# EMAX_12A.net
KiCad netlist of a schematic drawn in Altium Designer
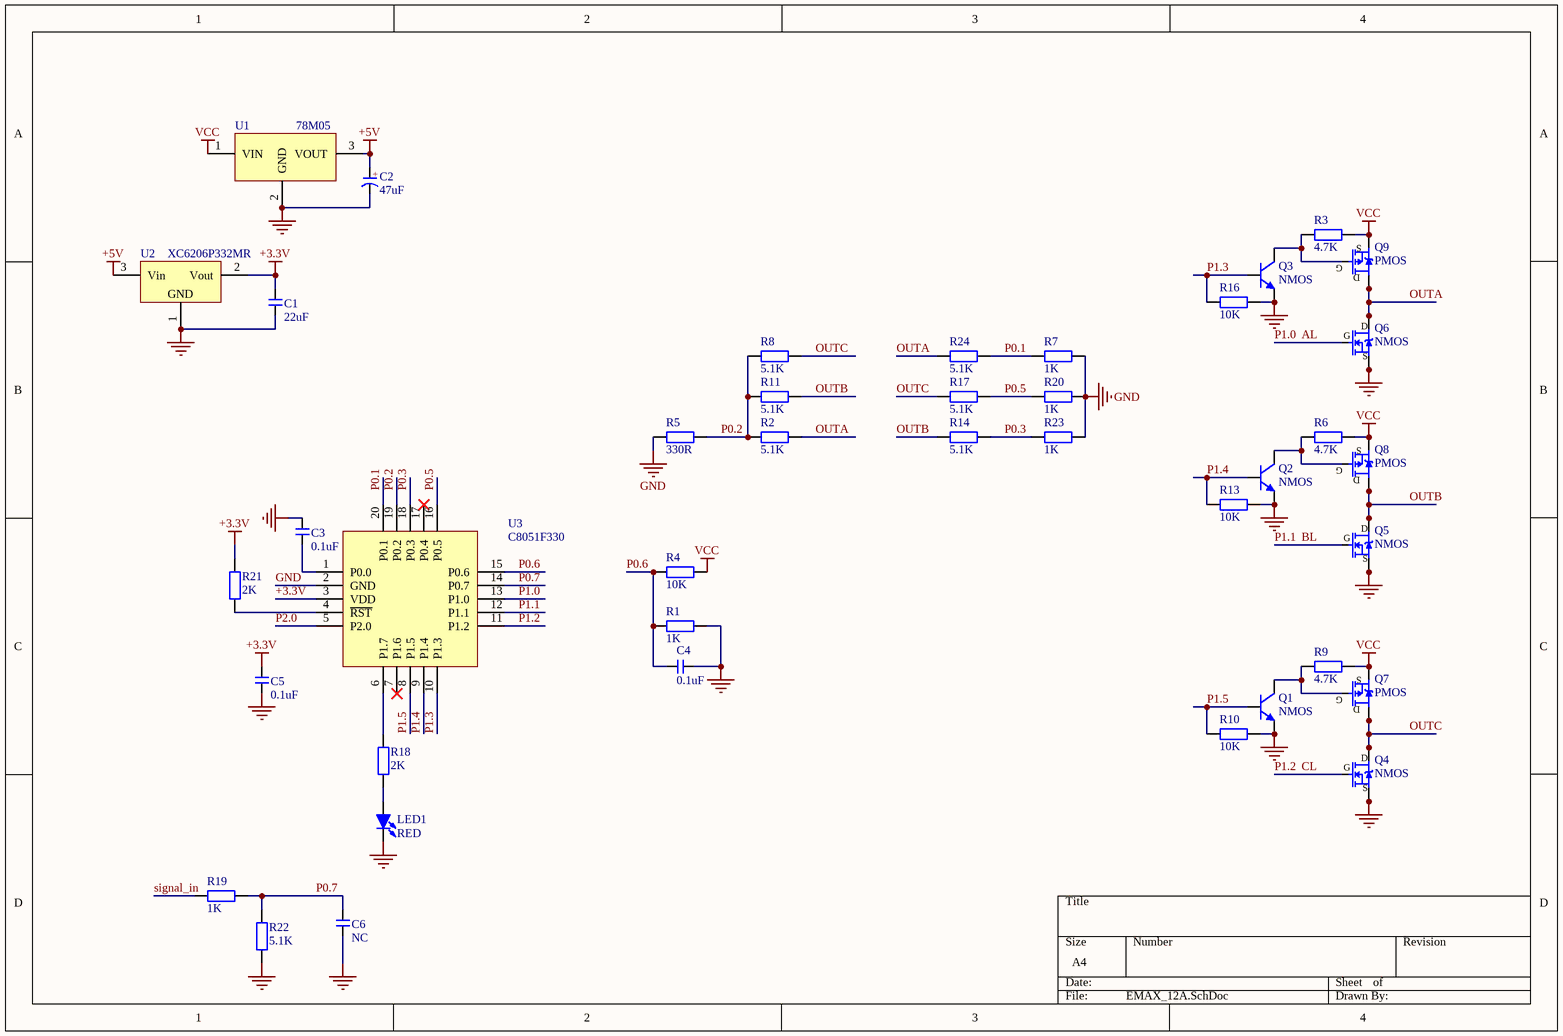
[diagram p0: EMAX_12A.SchDoc]

(export (version "E")
  (design (tool "Eeschema 10.0.6"))
  (components
    (comp (ref "C1")
      (value "22uF")
      (footprint "C 1206_L")
      (description "无极性贴片电容")
      (fields (field (name "版权归属") "源创客"))
      (libsource (lib "3.1   - 电阻-电容-电感") (part "C"))
    )
    (comp (ref "C2")
      (value "47uF")
      (footprint "CD B(3528)")
      (description "贴片钽电容")
      (fields (field (name "版权归属") "源创客"))
      (libsource (lib "3.1   - 电阻-电容-电感") (part "C-CD"))
    )
    (comp (ref "C3")
      (value "0.1uF")
      (footprint "C 0603_L")
      (description "无极性贴片电容")
      (fields (field (name "版权归属") "源创客"))
      (libsource (lib "3.1   - 电阻-电容-电感") (part "C"))
    )
    (comp (ref "C4")
      (value "0.1uF")
      (footprint "C 0603_L")
      (description "无极性贴片电容")
      (fields (field (name "版权归属") "源创客"))
      (libsource (lib "3.1   - 电阻-电容-电感") (part "C"))
    )
    (comp (ref "C5")
      (value "0.1uF")
      (footprint "C 0603_L")
      (description "无极性贴片电容")
      (fields (field (name "版权归属") "源创客"))
      (libsource (lib "3.1   - 电阻-电容-电感") (part "C"))
    )
    (comp (ref "C6")
      (value "NC")
      (footprint "C 0603_L")
      (description "无极性贴片电容")
      (fields (field (name "版权归属") "源创客"))
      (libsource (lib "3.1   - 电阻-电容-电感") (part "C"))
    )
    (comp (ref "LED1")
      (value "RED")
      (footprint "LED 0603R")
      (description "贴片LED")
      (fields (field (name "版权归属") "源创客"))
      (libsource (lib "9.1   - LED") (part "LED-SMD"))
    )
    (comp (ref "Q1")
      (value "NMOS")
      (footprint "LC-SOT-23(SOT-23-3)")
      (description "高频放大-NPN型")
      (fields (field (name "版权归属") "源创客"))
      (libsource (lib "6.2   - 三极管") (part "8050-SMD"))
    )
    (comp (ref "Q2")
      (value "NMOS")
      (footprint "LC-SOT-23(SOT-23-3)")
      (description "高频放大-NPN型")
      (fields (field (name "版权归属") "源创客"))
      (libsource (lib "6.2   - 三极管") (part "8050-SMD"))
    )
    (comp (ref "Q3")
      (value "NMOS")
      (footprint "LC-SOT-23(SOT-23-3)")
      (description "高频放大-NPN型")
      (fields (field (name "版权归属") "源创客"))
      (libsource (lib "6.2   - 三极管") (part "8050-SMD"))
    )
    (comp (ref "Q4")
      (value "NMOS")
      (footprint "LC-SOP-8_150mil")
      (fields (field (name "版权归属") "源创客"))
      (libsource (lib "6.1   - 场效应管-可控硅") (part "NMOS_DFN8_5x6"))
    )
    (comp (ref "Q5")
      (value "NMOS")
      (footprint "LC-SOP-8_150mil")
      (fields (field (name "版权归属") "源创客"))
      (libsource (lib "6.1   - 场效应管-可控硅") (part "NMOS_DFN8_5x6"))
    )
    (comp (ref "Q6")
      (value "NMOS")
      (footprint "LC-SOP-8_150mil")
      (fields (field (name "版权归属") "源创客"))
      (libsource (lib "6.1   - 场效应管-可控硅") (part "NMOS_DFN8_5x6"))
    )
    (comp (ref "Q7")
      (value "PMOS")
      (footprint "LC-SOP-8_150mil")
      (fields (field (name "版权归属") "源创客"))
      (libsource (lib "6.1   - 场效应管-可控硅") (part "PMOS_DFN8_5x6"))
    )
    (comp (ref "Q8")
      (value "PMOS")
      (footprint "LC-SOP-8_150mil")
      (fields (field (name "版权归属") "源创客"))
      (libsource (lib "6.1   - 场效应管-可控硅") (part "PMOS_DFN8_5x6"))
    )
    (comp (ref "Q9")
      (value "PMOS")
      (footprint "LC-SOP-8_150mil")
      (fields (field (name "版权归属") "源创客"))
      (libsource (lib "6.1   - 场效应管-可控硅") (part "PMOS_DFN8_5x6"))
    )
    (comp (ref "R1")
      (value "1K")
      (footprint "R 0603_L")
      (description "贴片电阻")
      (fields (field (name "版权归属") "源创客"))
      (libsource (lib "3.1   - 电阻-电容-电感") (part "R"))
    )
    (comp (ref "R2")
      (value "5.1K")
      (footprint "R 0603_L")
      (description "贴片电阻")
      (fields (field (name "版权归属") "源创客"))
      (libsource (lib "3.1   - 电阻-电容-电感") (part "R"))
    )
    (comp (ref "R3")
      (value "4.7K")
      (footprint "R 0603_L")
      (description "贴片电阻")
      (fields (field (name "版权归属") "源创客"))
      (libsource (lib "3.1   - 电阻-电容-电感") (part "R"))
    )
    (comp (ref "R4")
      (value "10K")
      (footprint "R 0603_L")
      (description "贴片电阻")
      (fields (field (name "版权归属") "源创客"))
      (libsource (lib "3.1   - 电阻-电容-电感") (part "R"))
    )
    (comp (ref "R5")
      (value "330R")
      (footprint "R 0603_L")
      (description "贴片电阻")
      (fields (field (name "版权归属") "源创客"))
      (libsource (lib "3.1   - 电阻-电容-电感") (part "R"))
    )
    (comp (ref "R6")
      (value "4.7K")
      (footprint "R 0603_L")
      (description "贴片电阻")
      (fields (field (name "版权归属") "源创客"))
      (libsource (lib "3.1   - 电阻-电容-电感") (part "R"))
    )
    (comp (ref "R7")
      (value "1K")
      (footprint "R 0603_L")
      (description "贴片电阻")
      (fields (field (name "版权归属") "源创客"))
      (libsource (lib "3.1   - 电阻-电容-电感") (part "R"))
    )
    (comp (ref "R8")
      (value "5.1K")
      (footprint "R 0603_L")
      (description "贴片电阻")
      (fields (field (name "版权归属") "源创客"))
      (libsource (lib "3.1   - 电阻-电容-电感") (part "R"))
    )
    (comp (ref "R9")
      (value "4.7K")
      (footprint "R 0603_L")
      (description "贴片电阻")
      (fields (field (name "版权归属") "源创客"))
      (libsource (lib "3.1   - 电阻-电容-电感") (part "R"))
    )
    (comp (ref "R10")
      (value "10K")
      (footprint "R 0603_L")
      (description "贴片电阻")
      (fields (field (name "版权归属") "源创客"))
      (libsource (lib "3.1   - 电阻-电容-电感") (part "R"))
    )
    (comp (ref "R11")
      (value "5.1K")
      (footprint "R 0603_L")
      (description "贴片电阻")
      (fields (field (name "版权归属") "源创客"))
      (libsource (lib "3.1   - 电阻-电容-电感") (part "R"))
    )
    (comp (ref "R13")
      (value "10K")
      (footprint "R 0603_L")
      (description "贴片电阻")
      (fields (field (name "版权归属") "源创客"))
      (libsource (lib "3.1   - 电阻-电容-电感") (part "R"))
    )
    (comp (ref "R14")
      (value "5.1K")
      (footprint "R 0603_L")
      (description "贴片电阻")
      (fields (field (name "版权归属") "源创客"))
      (libsource (lib "3.1   - 电阻-电容-电感") (part "R"))
    )
    (comp (ref "R16")
      (value "10K")
      (footprint "R 0603_L")
      (description "贴片电阻")
      (fields (field (name "版权归属") "源创客"))
      (libsource (lib "3.1   - 电阻-电容-电感") (part "R"))
    )
    (comp (ref "R17")
      (value "5.1K")
      (footprint "R 0603_L")
      (description "贴片电阻")
      (fields (field (name "版权归属") "源创客"))
      (libsource (lib "3.1   - 电阻-电容-电感") (part "R"))
    )
    (comp (ref "R18")
      (value "2K")
      (footprint "R 0603_L")
      (description "贴片电阻")
      (fields (field (name "版权归属") "源创客"))
      (libsource (lib "3.1   - 电阻-电容-电感") (part "R"))
    )
    (comp (ref "R19")
      (value "1K")
      (footprint "R 0603_L")
      (description "贴片电阻")
      (fields (field (name "版权归属") "源创客"))
      (libsource (lib "3.1   - 电阻-电容-电感") (part "R"))
    )
    (comp (ref "R20")
      (value "1K")
      (footprint "R 0603_L")
      (description "贴片电阻")
      (fields (field (name "版权归属") "源创客"))
      (libsource (lib "3.1   - 电阻-电容-电感") (part "R"))
    )
    (comp (ref "R21")
      (value "2K")
      (footprint "R 0603_L")
      (description "贴片电阻")
      (fields (field (name "版权归属") "源创客"))
      (libsource (lib "3.1   - 电阻-电容-电感") (part "R"))
    )
    (comp (ref "R22")
      (value "5.1K")
      (footprint "R 0603_L")
      (description "贴片电阻")
      (fields (field (name "版权归属") "源创客"))
      (libsource (lib "3.1   - 电阻-电容-电感") (part "R"))
    )
    (comp (ref "R23")
      (value "1K")
      (footprint "R 0603_L")
      (description "贴片电阻")
      (fields (field (name "版权归属") "源创客"))
      (libsource (lib "3.1   - 电阻-电容-电感") (part "R"))
    )
    (comp (ref "R24")
      (value "5.1K")
      (footprint "R 0603_L")
      (description "贴片电阻")
      (fields (field (name "版权归属") "源创客"))
      (libsource (lib "3.1   - 电阻-电容-电感") (part "R"))
    )
    (comp (ref "U1")
      (value "78M05")
      (footprint "LC-TO-252-2")
      (description "线性稳压芯片")
      (fields (field (name "版权归属") "源创客"))
      (libsource (lib "1.3   - 电源类芯片") (part "78xx"))
    )
    (comp (ref "U2")
      (value "XC6206P332MR")
      (footprint "LC-SOT-23(SOT-23-3)")
      (description "低压差线性稳压芯片")
      (fields (field (name "版权归属") "源创客"))
      (libsource (lib "1.3   - 电源类芯片") (part "XC6206P332MR"))
    )
    (comp (ref "U3")
      (value "C8051F330")
      (footprint "LC-QFN-20_4x4x05P")
      (libsource (lib "C8051") (part "C8051F330"))
    )
  )
  (nets
    (net (code "1") (name "+3.3V") (class "Default")
      (node (ref "C1") (pin "2") (pinfunction "2_2") (pintype "passive"))
      (node (ref "C5") (pin "2") (pinfunction "2_2") (pintype "passive"))
      (node (ref "R21") (pin "1") (pinfunction "1_1") (pintype "passive"))
      (node (ref "U2") (pin "2") (pinfunction "Vout_2") (pintype "passive"))
      (node (ref "U3") (pin "3") (pinfunction "VDD_3") (pintype "passive"))
    )
    (net (code "2") (name "+5V") (class "Default")
      (node (ref "C2") (pin "1") (pinfunction "A_1") (pintype "passive"))
      (node (ref "U1") (pin "3") (pinfunction "VOUT_3") (pintype "passive"))
      (node (ref "U2") (pin "3") (pinfunction "Vin_3") (pintype "passive"))
    )
    (net (code "3") (name "/AL") (class "Default")
      (node (ref "Q6") (pin "4") (pinfunction "G_4") (pintype "passive"))
      (node (ref "U3") (pin "13") (pinfunction "P1.0_13") (pintype "passive"))
    )
    (net (code "4") (name "/BL") (class "Default")
      (node (ref "Q5") (pin "4") (pinfunction "G_4") (pintype "passive"))
      (node (ref "U3") (pin "12") (pinfunction "P1.1_12") (pintype "passive"))
    )
    (net (code "5") (name "/CL") (class "Default")
      (node (ref "Q4") (pin "4") (pinfunction "G_4") (pintype "passive"))
      (node (ref "U3") (pin "11") (pinfunction "P1.2_11") (pintype "passive"))
    )
    (net (code "6") (name "/OUTA") (class "Default")
      (node (ref "Q6") (pin "5") (pinfunction "D_5") (pintype "passive"))
      (node (ref "Q6") (pin "6") (pinfunction "D_6") (pintype "passive"))
      (node (ref "Q6") (pin "7") (pinfunction "D_7") (pintype "passive"))
      (node (ref "Q6") (pin "8") (pinfunction "D_8") (pintype "passive"))
      (node (ref "Q9") (pin "5") (pinfunction "D_5") (pintype "passive"))
      (node (ref "Q9") (pin "6") (pinfunction "D_6") (pintype "passive"))
      (node (ref "Q9") (pin "7") (pinfunction "D_7") (pintype "passive"))
      (node (ref "Q9") (pin "8") (pinfunction "D_8") (pintype "passive"))
      (node (ref "R2") (pin "2") (pinfunction "2_2") (pintype "passive"))
      (node (ref "R24") (pin "2") (pinfunction "2_2") (pintype "passive"))
    )
    (net (code "7") (name "/OUTB") (class "Default")
      (node (ref "Q5") (pin "5") (pinfunction "D_5") (pintype "passive"))
      (node (ref "Q5") (pin "6") (pinfunction "D_6") (pintype "passive"))
      (node (ref "Q5") (pin "7") (pinfunction "D_7") (pintype "passive"))
      (node (ref "Q5") (pin "8") (pinfunction "D_8") (pintype "passive"))
      (node (ref "Q8") (pin "5") (pinfunction "D_5") (pintype "passive"))
      (node (ref "Q8") (pin "6") (pinfunction "D_6") (pintype "passive"))
      (node (ref "Q8") (pin "7") (pinfunction "D_7") (pintype "passive"))
      (node (ref "Q8") (pin "8") (pinfunction "D_8") (pintype "passive"))
      (node (ref "R11") (pin "2") (pinfunction "2_2") (pintype "passive"))
      (node (ref "R14") (pin "1") (pinfunction "1_1") (pintype "passive"))
    )
    (net (code "8") (name "/OUTC") (class "Default")
      (node (ref "Q4") (pin "5") (pinfunction "D_5") (pintype "passive"))
      (node (ref "Q4") (pin "6") (pinfunction "D_6") (pintype "passive"))
      (node (ref "Q4") (pin "7") (pinfunction "D_7") (pintype "passive"))
      (node (ref "Q4") (pin "8") (pinfunction "D_8") (pintype "passive"))
      (node (ref "Q7") (pin "5") (pinfunction "D_5") (pintype "passive"))
      (node (ref "Q7") (pin "6") (pinfunction "D_6") (pintype "passive"))
      (node (ref "Q7") (pin "7") (pinfunction "D_7") (pintype "passive"))
      (node (ref "Q7") (pin "8") (pinfunction "D_8") (pintype "passive"))
      (node (ref "R17") (pin "1") (pinfunction "1_1") (pintype "passive"))
      (node (ref "R8") (pin "2") (pinfunction "2_2") (pintype "passive"))
    )
    (net (code "9") (name "/P0.1") (class "Default")
      (node (ref "R24") (pin "1") (pinfunction "1_1") (pintype "passive"))
      (node (ref "R7") (pin "1") (pinfunction "1_1") (pintype "passive"))
      (node (ref "U3") (pin "20") (pinfunction "P0.1_20") (pintype "passive"))
    )
    (net (code "10") (name "/P0.2") (class "Default")
      (node (ref "R11") (pin "1") (pinfunction "1_1") (pintype "passive"))
      (node (ref "R2") (pin "1") (pinfunction "1_1") (pintype "passive"))
      (node (ref "R5") (pin "2") (pinfunction "2_2") (pintype "passive"))
      (node (ref "R8") (pin "1") (pinfunction "1_1") (pintype "passive"))
      (node (ref "U3") (pin "19") (pinfunction "P0.2_19") (pintype "passive"))
    )
    (net (code "11") (name "/P0.3") (class "Default")
      (node (ref "R14") (pin "2") (pinfunction "2_2") (pintype "passive"))
      (node (ref "R23") (pin "1") (pinfunction "1_1") (pintype "passive"))
      (node (ref "U3") (pin "18") (pinfunction "P0.3_18") (pintype "passive"))
    )
    (net (code "12") (name "/P0.5") (class "Default")
      (node (ref "R17") (pin "2") (pinfunction "2_2") (pintype "passive"))
      (node (ref "R20") (pin "1") (pinfunction "1_1") (pintype "passive"))
      (node (ref "U3") (pin "16") (pinfunction "P0.5_16") (pintype "passive"))
    )
    (net (code "13") (name "/P0.6") (class "Default")
      (node (ref "C4") (pin "1") (pinfunction "1_1") (pintype "passive"))
      (node (ref "R1") (pin "1") (pinfunction "1_1") (pintype "passive"))
      (node (ref "R4") (pin "1") (pinfunction "1_1") (pintype "passive"))
      (node (ref "U3") (pin "15") (pinfunction "P0.6_15") (pintype "passive"))
    )
    (net (code "14") (name "/P0.7") (class "Default")
      (node (ref "C6") (pin "2") (pinfunction "2_2") (pintype "passive"))
      (node (ref "R19") (pin "2") (pinfunction "2_2") (pintype "passive"))
      (node (ref "R22") (pin "1") (pinfunction "1_1") (pintype "passive"))
      (node (ref "U3") (pin "14") (pinfunction "P0.7_14") (pintype "passive"))
    )
    (net (code "15") (name "/P1.3") (class "Default")
      (node (ref "Q3") (pin "1") (pinfunction "B_1") (pintype "passive"))
      (node (ref "R16") (pin "2") (pinfunction "2_2") (pintype "passive"))
      (node (ref "U3") (pin "10") (pinfunction "P1.3_10") (pintype "passive"))
    )
    (net (code "16") (name "/P1.4") (class "Default")
      (node (ref "Q2") (pin "1") (pinfunction "B_1") (pintype "passive"))
      (node (ref "R13") (pin "1") (pinfunction "1_1") (pintype "passive"))
      (node (ref "U3") (pin "9") (pinfunction "P1.4_9") (pintype "passive"))
    )
    (net (code "17") (name "/P1.5") (class "Default")
      (node (ref "Q1") (pin "1") (pinfunction "B_1") (pintype "passive"))
      (node (ref "R10") (pin "1") (pinfunction "1_1") (pintype "passive"))
      (node (ref "U3") (pin "8") (pinfunction "P1.5_8") (pintype "passive"))
    )
    (net (code "18") (name "/P2.0") (class "Default")
      (node (ref "U3") (pin "5") (pinfunction "P2.0_5") (pintype "passive"))
    )
    (net (code "19") (name "/signal_in") (class "Default")
      (node (ref "R19") (pin "1") (pinfunction "1_1") (pintype "passive"))
    )
    (net (code "20") (name "GND") (class "Default")
      (node (ref "C1") (pin "1") (pinfunction "1_1") (pintype "passive"))
      (node (ref "C2") (pin "2") (pinfunction "K_2") (pintype "passive"))
      (node (ref "C3") (pin "2") (pinfunction "2_2") (pintype "passive"))
      (node (ref "C4") (pin "2") (pinfunction "2_2") (pintype "passive"))
      (node (ref "C5") (pin "1") (pinfunction "1_1") (pintype "passive"))
      (node (ref "C6") (pin "1") (pinfunction "1_1") (pintype "passive"))
      (node (ref "LED1") (pin "2") (pinfunction "K_2") (pintype "passive"))
      (node (ref "Q1") (pin "2") (pinfunction "E_2") (pintype "passive"))
      (node (ref "Q2") (pin "2") (pinfunction "E_2") (pintype "passive"))
      (node (ref "Q3") (pin "2") (pinfunction "E_2") (pintype "passive"))
      (node (ref "Q4") (pin "1") (pinfunction "S_1") (pintype "passive"))
      (node (ref "Q4") (pin "2") (pinfunction "S_2") (pintype "passive"))
      (node (ref "Q4") (pin "3") (pinfunction "S_3") (pintype "passive"))
      (node (ref "Q5") (pin "1") (pinfunction "S_1") (pintype "passive"))
      (node (ref "Q5") (pin "2") (pinfunction "S_2") (pintype "passive"))
      (node (ref "Q5") (pin "3") (pinfunction "S_3") (pintype "passive"))
      (node (ref "Q6") (pin "1") (pinfunction "S_1") (pintype "passive"))
      (node (ref "Q6") (pin "2") (pinfunction "S_2") (pintype "passive"))
      (node (ref "Q6") (pin "3") (pinfunction "S_3") (pintype "passive"))
      (node (ref "R1") (pin "2") (pinfunction "2_2") (pintype "passive"))
      (node (ref "R10") (pin "2") (pinfunction "2_2") (pintype "passive"))
      (node (ref "R13") (pin "2") (pinfunction "2_2") (pintype "passive"))
      (node (ref "R16") (pin "1") (pinfunction "1_1") (pintype "passive"))
      (node (ref "R20") (pin "2") (pinfunction "2_2") (pintype "passive"))
      (node (ref "R22") (pin "2") (pinfunction "2_2") (pintype "passive"))
      (node (ref "R23") (pin "2") (pinfunction "2_2") (pintype "passive"))
      (node (ref "R5") (pin "1") (pinfunction "1_1") (pintype "passive"))
      (node (ref "R7") (pin "2") (pinfunction "2_2") (pintype "passive"))
      (node (ref "U1") (pin "2") (pinfunction "GND_2") (pintype "passive"))
      (node (ref "U2") (pin "1") (pinfunction "GND_1") (pintype "passive"))
      (node (ref "U3") (pin "2") (pinfunction "GND_2") (pintype "passive"))
    )
    (net (code "21") (name "Net-(LED1-A)") (class "Default")
      (node (ref "LED1") (pin "1") (pinfunction "A_1") (pintype "passive"))
      (node (ref "R18") (pin "1") (pinfunction "1_1") (pintype "passive"))
    )
    (net (code "22") (name "Net-(Q1-C)") (class "Default")
      (node (ref "Q1") (pin "3") (pinfunction "C_3") (pintype "passive"))
      (node (ref "Q7") (pin "4") (pinfunction "G_4") (pintype "passive"))
      (node (ref "R9") (pin "2") (pinfunction "2_2") (pintype "passive"))
    )
    (net (code "23") (name "Net-(Q2-C)") (class "Default")
      (node (ref "Q2") (pin "3") (pinfunction "C_3") (pintype "passive"))
      (node (ref "Q8") (pin "4") (pinfunction "G_4") (pintype "passive"))
      (node (ref "R6") (pin "2") (pinfunction "2_2") (pintype "passive"))
    )
    (net (code "24") (name "Net-(Q3-C)") (class "Default")
      (node (ref "Q3") (pin "3") (pinfunction "C_3") (pintype "passive"))
      (node (ref "Q9") (pin "4") (pinfunction "G_4") (pintype "passive"))
      (node (ref "R3") (pin "2") (pinfunction "2_2") (pintype "passive"))
    )
    (net (code "25") (name "Net-(U3-P0.0)") (class "Default")
      (node (ref "C3") (pin "1") (pinfunction "1_1") (pintype "passive"))
      (node (ref "U3") (pin "1") (pinfunction "P0.0_1") (pintype "passive"))
    )
    (net (code "26") (name "Net-(U3-P1.7)") (class "Default")
      (node (ref "R18") (pin "2") (pinfunction "2_2") (pintype "passive"))
      (node (ref "U3") (pin "6") (pinfunction "P1.7_6") (pintype "passive"))
    )
    (net (code "27") (name "Net-(U3-~{RST})") (class "Default")
      (node (ref "R21") (pin "2") (pinfunction "2_2") (pintype "passive"))
      (node (ref "U3") (pin "4") (pinfunction "~{RST}_4") (pintype "passive"))
    )
    (net (code "28") (name "VCC") (class "Default")
      (node (ref "Q7") (pin "1") (pinfunction "S_1") (pintype "passive"))
      (node (ref "Q7") (pin "2") (pinfunction "S_2") (pintype "passive"))
      (node (ref "Q7") (pin "3") (pinfunction "S_3") (pintype "passive"))
      (node (ref "Q8") (pin "1") (pinfunction "S_1") (pintype "passive"))
      (node (ref "Q8") (pin "2") (pinfunction "S_2") (pintype "passive"))
      (node (ref "Q8") (pin "3") (pinfunction "S_3") (pintype "passive"))
      (node (ref "Q9") (pin "1") (pinfunction "S_1") (pintype "passive"))
      (node (ref "Q9") (pin "2") (pinfunction "S_2") (pintype "passive"))
      (node (ref "Q9") (pin "3") (pinfunction "S_3") (pintype "passive"))
      (node (ref "R3") (pin "1") (pinfunction "1_1") (pintype "passive"))
      (node (ref "R4") (pin "2") (pinfunction "2_2") (pintype "passive"))
      (node (ref "R6") (pin "1") (pinfunction "1_1") (pintype "passive"))
      (node (ref "R9") (pin "1") (pinfunction "1_1") (pintype "passive"))
      (node (ref "U1") (pin "1") (pinfunction "VIN_1") (pintype "passive"))
    )
    (net (code "29") (name "unconnected-(U3-P0.4-Pad17)") (class "Default")
      (node (ref "U3") (pin "17") (pinfunction "P0.4_17") (pintype "passive+no_connect"))
    )
    (net (code "30") (name "unconnected-(U3-P1.6-Pad7)") (class "Default")
      (node (ref "U3") (pin "7") (pinfunction "P1.6_7") (pintype "passive+no_connect"))
    )
  )
)
